# 7_Display.net
KiCad netlist of a schematic drawn in Altium Designer
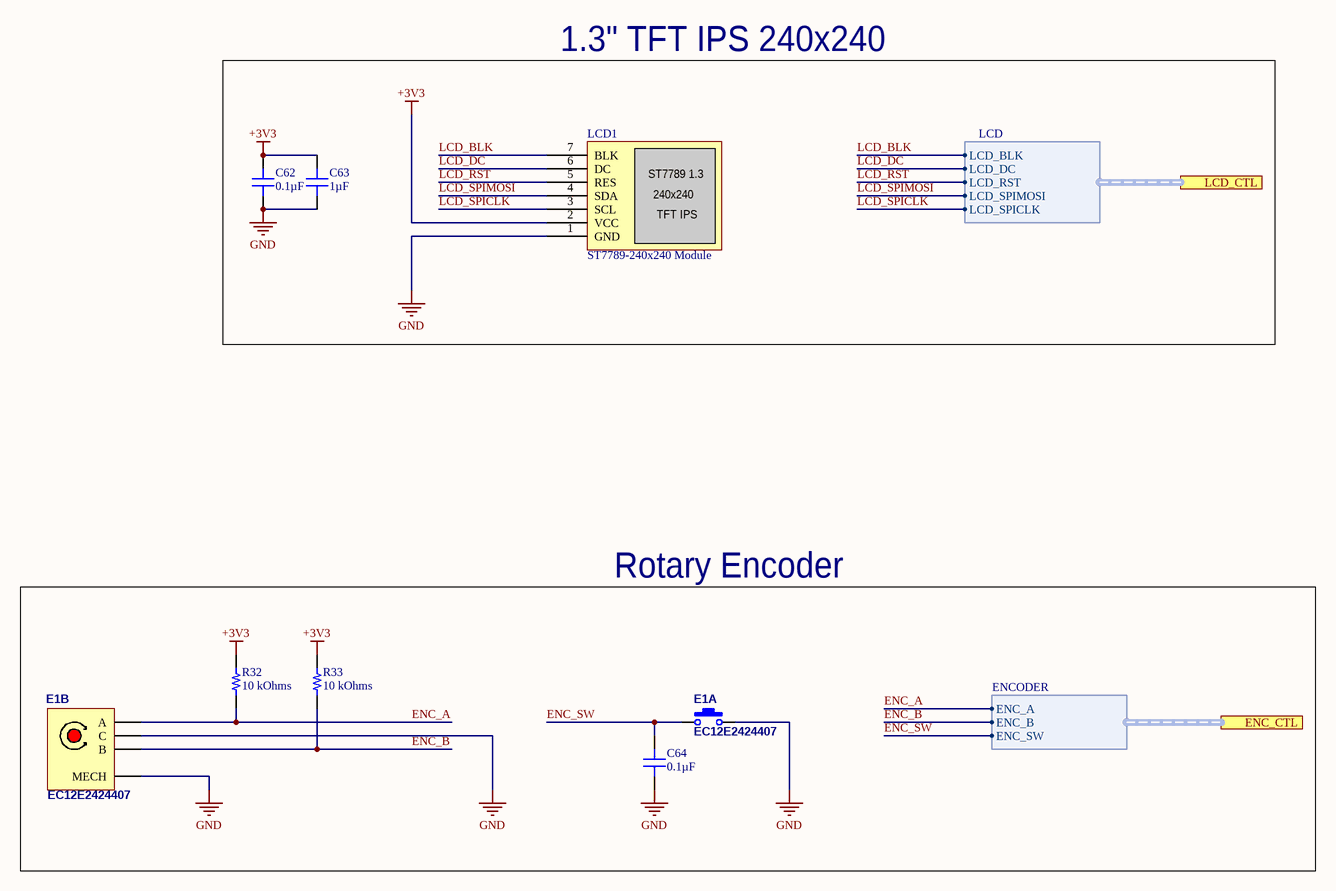
[diagram p0: [7] Display.SchDoc]

(export (version "E")
  (design (tool "Eeschema 10.0.6"))
  (components
    (comp (ref "C62")
      (value "0.1µF")
      (footprint "CAP 0603_1608")
      (description "CAP CER 0.1UF 50V X7R 0603")
      (fields (field (name "PART NUMBER") "0603BB104K500NGT") (field (name "MANUFACTURER") "Knowles Novacap"))
      (libsource (lib "Celestial Altium Library - altium_library") (part "Capacitor"))
    )
    (comp (ref "C63")
      (value "1µF")
      (footprint "CAP 0603_1608")
      (description "CAP CER 1UF 16V X7R 0603")
      (fields (field (name "PART NUMBER") "0603BB105K160YT") (field (name "MANUFACTURER") "Knowles Novacap"))
      (libsource (lib "Celestial Altium Library - altium_library") (part "Capacitor"))
    )
    (comp (ref "C64")
      (value "0.1µF")
      (footprint "CAP 0603_1608")
      (description "CAP CER 0.1UF 50V X7R 0603")
      (fields (field (name "PART NUMBER") "0603BB104K500NGT") (field (name "MANUFACTURER") "Knowles Novacap"))
      (libsource (lib "Celestial Altium Library - altium_library") (part "Capacitor"))
    )
    (comp (ref "E1")
      (value "EC12E2424407")
      (footprint "EC12E242")
      (description "Alps 20mm, 24PPR+SW Encoder")
      (libsource (lib "encoders") (part "EC12E2424407"))
    )
    (comp (ref "LCD1")
      (value "ST7789-240x240 Module")
      (footprint "1.3 TFT IPS - Module")
      (description "LCD TFT IPS 1.3\" 240x240")
      (libsource (lib "Celestial Library Database") (part "ST7789 1.3 IPS 240x240"))
    )
    (comp (ref "R32")
      (value "10 kOhms")
      (footprint "RES 0603_1608")
      (description "RES SMD 10K OHM 5% 1/10W 0603")
      (fields (field (name "PART NUMBER") "CRCW060310K0JNEA") (field (name "MANUFACTURER") "Vishay Dale"))
      (libsource (lib "Celestial Altium Library - altium_library") (part "Resistor"))
    )
    (comp (ref "R33")
      (value "10 kOhms")
      (footprint "RES 0603_1608")
      (description "RES SMD 10K OHM 5% 1/10W 0603")
      (fields (field (name "PART NUMBER") "CRCW060310K0JNEA") (field (name "MANUFACTURER") "Vishay Dale"))
      (libsource (lib "Celestial Altium Library - altium_library") (part "Resistor"))
    )
  )
  (nets
    (net (code "3") (name "+3V3") (class "Default")
      (node (ref "C62") (pin "1") (pinfunction "1_1") (pintype "passive"))
      (node (ref "C63") (pin "2") (pinfunction "2_2") (pintype "passive"))
      (node (ref "LCD1") (pin "2") (pinfunction "VCC_2") (pintype "passive"))
      (node (ref "R32") (pin "2") (pinfunction "2_2") (pintype "passive"))
      (node (ref "R33") (pin "2") (pinfunction "2_2") (pintype "passive"))
    )
    (net (code "4") (name "/ENC_A") (class "Default")
      (node (ref "E1") (pin "A") (pinfunction "A_A") (pintype "passive"))
      (node (ref "R32") (pin "1") (pinfunction "1_1") (pintype "passive"))
    )
    (net (code "5") (name "/ENC_B") (class "Default")
      (node (ref "E1") (pin "B") (pinfunction "B_B") (pintype "passive"))
      (node (ref "R33") (pin "1") (pinfunction "1_1") (pintype "passive"))
    )
    (net (code "6") (name "/ENC_SW") (class "Default")
      (node (ref "C64") (pin "1") (pinfunction "1_1") (pintype "passive"))
      (node (ref "E1") (pin "S1") (pinfunction "S1_S1") (pintype "passive"))
    )
    (net (code "7") (name "/LCD_BLK") (class "Default")
      (node (ref "LCD1") (pin "7") (pinfunction "BLK_7") (pintype "passive"))
    )
    (net (code "8") (name "/LCD_DC") (class "Default")
      (node (ref "LCD1") (pin "6") (pinfunction "DC_6") (pintype "passive"))
    )
    (net (code "9") (name "/LCD_RST") (class "Default")
      (node (ref "LCD1") (pin "5") (pinfunction "RES_5") (pintype "passive"))
    )
    (net (code "10") (name "/LCD_SPICLK") (class "Default")
      (node (ref "LCD1") (pin "3") (pinfunction "SCL_3") (pintype "passive"))
    )
    (net (code "11") (name "/LCD_SPIMOSI") (class "Default")
      (node (ref "LCD1") (pin "4") (pinfunction "SDA_4") (pintype "passive"))
    )
    (net (code "14") (name "GND") (class "Default")
      (node (ref "C62") (pin "2") (pinfunction "2_2") (pintype "passive"))
      (node (ref "C63") (pin "1") (pinfunction "1_1") (pintype "passive"))
      (node (ref "C64") (pin "2") (pinfunction "2_2") (pintype "passive"))
      (node (ref "E1") (pin "C") (pinfunction "C_C") (pintype "passive"))
      (node (ref "E1") (pin "M") (pinfunction "MECH_M") (pintype "passive"))
      (node (ref "E1") (pin "S2") (pinfunction "S2_S2") (pintype "passive"))
      (node (ref "LCD1") (pin "1") (pinfunction "GND_1") (pintype "passive"))
    )
  )
)
